# esquematico.net
KiCad netlist of a schematic drawn in EAGLE
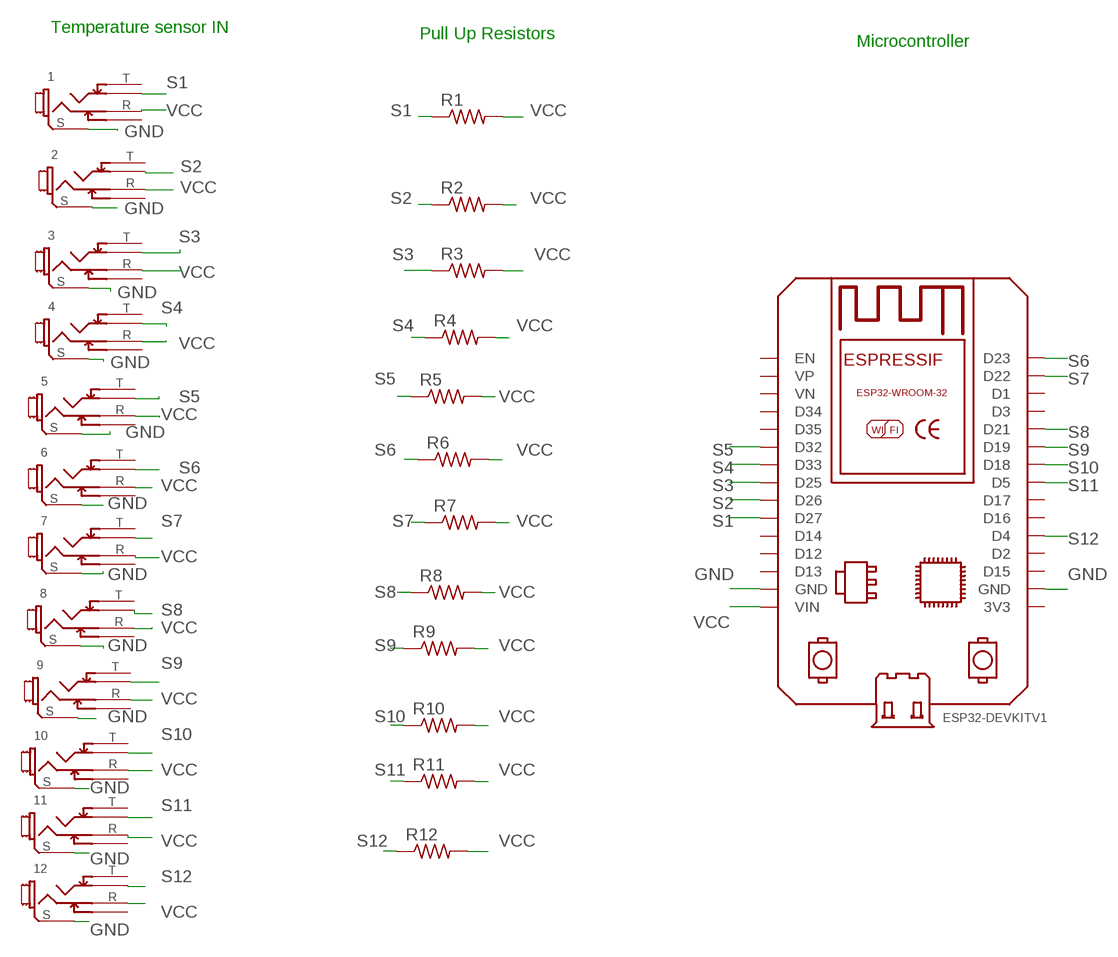
[diagram p0: schematic, sheet 1]

(export (version "E")
  (design (tool "Eeschema 10.0.6"))
  (components
    (comp (ref "1")
      (value "JACK-3.5MM")
      (footprint "eagle-import:JACK-5PINES")
      (libsource (lib "eagle-import") (part "JACK-3.5MM"))
    )
    (comp (ref "2")
      (value "JACK-3.5MM")
      (footprint "eagle-import:JACK-5PINES")
      (libsource (lib "eagle-import") (part "JACK-3.5MM"))
    )
    (comp (ref "3")
      (value "JACK-3.5MM")
      (footprint "eagle-import:JACK-5PINES")
      (libsource (lib "eagle-import") (part "JACK-3.5MM"))
    )
    (comp (ref "4")
      (value "JACK-3.5MM")
      (footprint "eagle-import:JACK-5PINES")
      (libsource (lib "eagle-import") (part "JACK-3.5MM"))
    )
    (comp (ref "5")
      (value "JACK-3.5MM")
      (footprint "eagle-import:JACK-5PINES")
      (libsource (lib "eagle-import") (part "JACK-3.5MM"))
    )
    (comp (ref "6")
      (value "JACK-3.5MM")
      (footprint "eagle-import:JACK-5PINES")
      (libsource (lib "eagle-import") (part "JACK-3.5MM"))
    )
    (comp (ref "7")
      (value "JACK-3.5MM")
      (footprint "eagle-import:JACK-5PINES")
      (libsource (lib "eagle-import") (part "JACK-3.5MM"))
    )
    (comp (ref "8")
      (value "JACK-3.5MM")
      (footprint "eagle-import:JACK-5PINES")
      (libsource (lib "eagle-import") (part "JACK-3.5MM"))
    )
    (comp (ref "9")
      (value "JACK-3.5MM")
      (footprint "eagle-import:JACK-5PINES")
      (libsource (lib "eagle-import") (part "JACK-3.5MM"))
    )
    (comp (ref "10")
      (value "JACK-3.5MM")
      (footprint "eagle-import:JACK-5PINES")
      (libsource (lib "eagle-import") (part "JACK-3.5MM"))
    )
    (comp (ref "11")
      (value "JACK-3.5MM")
      (footprint "eagle-import:JACK-5PINES")
      (libsource (lib "eagle-import") (part "JACK-3.5MM"))
    )
    (comp (ref "12")
      (value "JACK-3.5MM")
      (footprint "eagle-import:JACK-5PINES")
      (libsource (lib "eagle-import") (part "JACK-3.5MM"))
    )
    (comp (ref "BOARD1")
      (value "ESP32DEVKITV1")
      (footprint "eagle-import:ESP32-DEVKITV1")
      (libsource (lib "eagle-import") (part "ESP32DEVKITV1"))
    )
    (comp (ref "R1")
      (value "R-US_M0805")
      (footprint "eagle-import:M0805")
      (libsource (lib "eagle-import") (part "R-US_M0805"))
    )
    (comp (ref "R2")
      (value "R-US_M0805")
      (footprint "eagle-import:M0805")
      (libsource (lib "eagle-import") (part "R-US_M0805"))
    )
    (comp (ref "R3")
      (value "R-US_M0805")
      (footprint "eagle-import:M0805")
      (libsource (lib "eagle-import") (part "R-US_M0805"))
    )
    (comp (ref "R4")
      (value "R-US_M0805")
      (footprint "eagle-import:M0805")
      (libsource (lib "eagle-import") (part "R-US_M0805"))
    )
    (comp (ref "R5")
      (value "R-US_M0805")
      (footprint "eagle-import:M0805")
      (libsource (lib "eagle-import") (part "R-US_M0805"))
    )
    (comp (ref "R6")
      (value "R-US_M0805")
      (footprint "eagle-import:M0805")
      (libsource (lib "eagle-import") (part "R-US_M0805"))
    )
    (comp (ref "R7")
      (value "R-US_M0805")
      (footprint "eagle-import:M0805")
      (libsource (lib "eagle-import") (part "R-US_M0805"))
    )
    (comp (ref "R8")
      (value "R-US_M0805")
      (footprint "eagle-import:M0805")
      (libsource (lib "eagle-import") (part "R-US_M0805"))
    )
    (comp (ref "R9")
      (value "R-US_M0805")
      (footprint "eagle-import:M0805")
      (libsource (lib "eagle-import") (part "R-US_M0805"))
    )
    (comp (ref "R10")
      (value "R-US_M0805")
      (footprint "eagle-import:M0805")
      (libsource (lib "eagle-import") (part "R-US_M0805"))
    )
    (comp (ref "R11")
      (value "R-US_M0805")
      (footprint "eagle-import:M0805")
      (libsource (lib "eagle-import") (part "R-US_M0805"))
    )
    (comp (ref "R12")
      (value "R-US_M0805")
      (footprint "eagle-import:M0805")
      (libsource (lib "eagle-import") (part "R-US_M0805"))
    )
  )
  (nets
    (net (code "1") (name "/GND") (class "Default")
      (node (ref "1") (pin "S") (pinfunction "S_S") (pintype "power_in"))
      (node (ref "10") (pin "S") (pinfunction "S_S") (pintype "power_in"))
      (node (ref "11") (pin "S") (pinfunction "S_S") (pintype "power_in"))
      (node (ref "12") (pin "S") (pinfunction "S_S") (pintype "power_in"))
      (node (ref "2") (pin "S") (pinfunction "S_S") (pintype "power_in"))
      (node (ref "3") (pin "S") (pinfunction "S_S") (pintype "power_in"))
      (node (ref "4") (pin "S") (pinfunction "S_S") (pintype "power_in"))
      (node (ref "5") (pin "S") (pinfunction "S_S") (pintype "power_in"))
      (node (ref "6") (pin "S") (pinfunction "S_S") (pintype "power_in"))
      (node (ref "7") (pin "S") (pinfunction "S_S") (pintype "power_in"))
      (node (ref "8") (pin "S") (pinfunction "S_S") (pintype "power_in"))
      (node (ref "9") (pin "S") (pinfunction "S_S") (pintype "power_in"))
      (node (ref "BOARD1") (pin "GND") (pinfunction "GND_GND") (pintype "bidirectional"))
      (node (ref "BOARD1") (pin "GND@1") (pinfunction "GND_GND@1") (pintype "bidirectional"))
    )
    (net (code "2") (name "/S1") (class "Default")
      (node (ref "1") (pin "T") (pinfunction "T_T") (pintype "bidirectional"))
      (node (ref "BOARD1") (pin "D27") (pinfunction "D27_D27") (pintype "bidirectional"))
      (node (ref "R1") (pin "1") (pinfunction "1_1") (pintype "passive"))
    )
    (net (code "3") (name "/S2") (class "Default")
      (node (ref "2") (pin "T") (pinfunction "T_T") (pintype "bidirectional"))
      (node (ref "BOARD1") (pin "D26") (pinfunction "D26_D26") (pintype "bidirectional"))
      (node (ref "R2") (pin "1") (pinfunction "1_1") (pintype "passive"))
    )
    (net (code "4") (name "/S3") (class "Default")
      (node (ref "3") (pin "T") (pinfunction "T_T") (pintype "bidirectional"))
      (node (ref "BOARD1") (pin "D25") (pinfunction "D25_D25") (pintype "bidirectional"))
      (node (ref "R3") (pin "1") (pinfunction "1_1") (pintype "passive"))
    )
    (net (code "5") (name "/S4") (class "Default")
      (node (ref "4") (pin "T") (pinfunction "T_T") (pintype "bidirectional"))
      (node (ref "BOARD1") (pin "D33") (pinfunction "D33_D33") (pintype "bidirectional"))
      (node (ref "R4") (pin "1") (pinfunction "1_1") (pintype "passive"))
    )
    (net (code "6") (name "/S5") (class "Default")
      (node (ref "5") (pin "T") (pinfunction "T_T") (pintype "bidirectional"))
      (node (ref "BOARD1") (pin "D32") (pinfunction "D32_D32") (pintype "bidirectional"))
      (node (ref "R5") (pin "1") (pinfunction "1_1") (pintype "passive"))
    )
    (net (code "7") (name "/S6") (class "Default")
      (node (ref "6") (pin "T") (pinfunction "T_T") (pintype "bidirectional"))
      (node (ref "BOARD1") (pin "D23") (pinfunction "D23_D23") (pintype "bidirectional"))
      (node (ref "R6") (pin "1") (pinfunction "1_1") (pintype "passive"))
    )
    (net (code "8") (name "/S7") (class "Default")
      (node (ref "7") (pin "T") (pinfunction "T_T") (pintype "bidirectional"))
      (node (ref "BOARD1") (pin "D22") (pinfunction "D22_D22") (pintype "bidirectional"))
      (node (ref "R7") (pin "1") (pinfunction "1_1") (pintype "passive"))
    )
    (net (code "9") (name "/S8") (class "Default")
      (node (ref "8") (pin "T") (pinfunction "T_T") (pintype "bidirectional"))
      (node (ref "BOARD1") (pin "D21") (pinfunction "D21_D21") (pintype "bidirectional"))
      (node (ref "R8") (pin "1") (pinfunction "1_1") (pintype "passive"))
    )
    (net (code "10") (name "/S9") (class "Default")
      (node (ref "9") (pin "T") (pinfunction "T_T") (pintype "bidirectional"))
      (node (ref "BOARD1") (pin "D19") (pinfunction "D19_D19") (pintype "bidirectional"))
      (node (ref "R9") (pin "1") (pinfunction "1_1") (pintype "passive"))
    )
    (net (code "11") (name "/S10") (class "Default")
      (node (ref "10") (pin "T") (pinfunction "T_T") (pintype "bidirectional"))
      (node (ref "BOARD1") (pin "D18") (pinfunction "D18_D18") (pintype "bidirectional"))
      (node (ref "R10") (pin "1") (pinfunction "1_1") (pintype "passive"))
    )
    (net (code "12") (name "/S11") (class "Default")
      (node (ref "11") (pin "T") (pinfunction "T_T") (pintype "bidirectional"))
      (node (ref "BOARD1") (pin "D5") (pinfunction "D5_D5") (pintype "bidirectional"))
      (node (ref "R11") (pin "1") (pinfunction "1_1") (pintype "passive"))
    )
    (net (code "13") (name "/S12") (class "Default")
      (node (ref "12") (pin "T") (pinfunction "T_T") (pintype "bidirectional"))
      (node (ref "BOARD1") (pin "D4") (pinfunction "D4_D4") (pintype "bidirectional"))
      (node (ref "R12") (pin "1") (pinfunction "1_1") (pintype "passive"))
    )
    (net (code "14") (name "/VCC") (class "Default")
      (node (ref "1") (pin "R") (pinfunction "R_R") (pintype "bidirectional"))
      (node (ref "10") (pin "R") (pinfunction "R_R") (pintype "bidirectional"))
      (node (ref "11") (pin "R") (pinfunction "R_R") (pintype "bidirectional"))
      (node (ref "12") (pin "R") (pinfunction "R_R") (pintype "bidirectional"))
      (node (ref "2") (pin "R") (pinfunction "R_R") (pintype "bidirectional"))
      (node (ref "3") (pin "R") (pinfunction "R_R") (pintype "bidirectional"))
      (node (ref "4") (pin "R") (pinfunction "R_R") (pintype "bidirectional"))
      (node (ref "5") (pin "R") (pinfunction "R_R") (pintype "bidirectional"))
      (node (ref "6") (pin "R") (pinfunction "R_R") (pintype "bidirectional"))
      (node (ref "7") (pin "R") (pinfunction "R_R") (pintype "bidirectional"))
      (node (ref "8") (pin "R") (pinfunction "R_R") (pintype "bidirectional"))
      (node (ref "9") (pin "R") (pinfunction "R_R") (pintype "bidirectional"))
      (node (ref "BOARD1") (pin "VIN") (pinfunction "VIN_VIN") (pintype "bidirectional"))
      (node (ref "R1") (pin "2") (pinfunction "2_2") (pintype "passive"))
      (node (ref "R10") (pin "2") (pinfunction "2_2") (pintype "passive"))
      (node (ref "R11") (pin "2") (pinfunction "2_2") (pintype "passive"))
      (node (ref "R12") (pin "2") (pinfunction "2_2") (pintype "passive"))
      (node (ref "R2") (pin "2") (pinfunction "2_2") (pintype "passive"))
      (node (ref "R3") (pin "2") (pinfunction "2_2") (pintype "passive"))
      (node (ref "R4") (pin "2") (pinfunction "2_2") (pintype "passive"))
      (node (ref "R5") (pin "2") (pinfunction "2_2") (pintype "passive"))
      (node (ref "R6") (pin "2") (pinfunction "2_2") (pintype "passive"))
      (node (ref "R7") (pin "2") (pinfunction "2_2") (pintype "passive"))
      (node (ref "R8") (pin "2") (pinfunction "2_2") (pintype "passive"))
      (node (ref "R9") (pin "2") (pinfunction "2_2") (pintype "passive"))
    )
    (net (code "15") (name "unconnected-(1-PadRS)") (class "Default")
      (node (ref "1") (pin "RS") (pinfunction "RS_RS") (pintype "bidirectional"))
    )
    (net (code "16") (name "unconnected-(1-PadTS)") (class "Default")
      (node (ref "1") (pin "TS") (pinfunction "TS_TS") (pintype "bidirectional"))
    )
    (net (code "17") (name "unconnected-(2-PadRS)") (class "Default")
      (node (ref "2") (pin "RS") (pinfunction "RS_RS") (pintype "bidirectional"))
    )
    (net (code "18") (name "unconnected-(2-PadTS)") (class "Default")
      (node (ref "2") (pin "TS") (pinfunction "TS_TS") (pintype "bidirectional"))
    )
    (net (code "19") (name "unconnected-(3-PadRS)") (class "Default")
      (node (ref "3") (pin "RS") (pinfunction "RS_RS") (pintype "bidirectional"))
    )
    (net (code "20") (name "unconnected-(3-PadTS)") (class "Default")
      (node (ref "3") (pin "TS") (pinfunction "TS_TS") (pintype "bidirectional"))
    )
    (net (code "21") (name "unconnected-(4-PadRS)") (class "Default")
      (node (ref "4") (pin "RS") (pinfunction "RS_RS") (pintype "bidirectional"))
    )
    (net (code "22") (name "unconnected-(4-PadTS)") (class "Default")
      (node (ref "4") (pin "TS") (pinfunction "TS_TS") (pintype "bidirectional"))
    )
    (net (code "23") (name "unconnected-(5-PadRS)") (class "Default")
      (node (ref "5") (pin "RS") (pinfunction "RS_RS") (pintype "bidirectional"))
    )
    (net (code "24") (name "unconnected-(5-PadTS)") (class "Default")
      (node (ref "5") (pin "TS") (pinfunction "TS_TS") (pintype "bidirectional"))
    )
    (net (code "25") (name "unconnected-(6-PadRS)") (class "Default")
      (node (ref "6") (pin "RS") (pinfunction "RS_RS") (pintype "bidirectional"))
    )
    (net (code "26") (name "unconnected-(6-PadTS)") (class "Default")
      (node (ref "6") (pin "TS") (pinfunction "TS_TS") (pintype "bidirectional"))
    )
    (net (code "27") (name "unconnected-(7-PadRS)") (class "Default")
      (node (ref "7") (pin "RS") (pinfunction "RS_RS") (pintype "bidirectional"))
    )
    (net (code "28") (name "unconnected-(7-PadTS)") (class "Default")
      (node (ref "7") (pin "TS") (pinfunction "TS_TS") (pintype "bidirectional"))
    )
    (net (code "29") (name "unconnected-(8-PadRS)") (class "Default")
      (node (ref "8") (pin "RS") (pinfunction "RS_RS") (pintype "bidirectional"))
    )
    (net (code "30") (name "unconnected-(8-PadTS)") (class "Default")
      (node (ref "8") (pin "TS") (pinfunction "TS_TS") (pintype "bidirectional"))
    )
    (net (code "31") (name "unconnected-(9-PadRS)") (class "Default")
      (node (ref "9") (pin "RS") (pinfunction "RS_RS") (pintype "bidirectional"))
    )
    (net (code "32") (name "unconnected-(9-PadTS)") (class "Default")
      (node (ref "9") (pin "TS") (pinfunction "TS_TS") (pintype "bidirectional"))
    )
    (net (code "33") (name "unconnected-(10-PadRS)") (class "Default")
      (node (ref "10") (pin "RS") (pinfunction "RS_RS") (pintype "bidirectional"))
    )
    (net (code "34") (name "unconnected-(10-PadTS)") (class "Default")
      (node (ref "10") (pin "TS") (pinfunction "TS_TS") (pintype "bidirectional"))
    )
    (net (code "35") (name "unconnected-(11-PadRS)") (class "Default")
      (node (ref "11") (pin "RS") (pinfunction "RS_RS") (pintype "bidirectional"))
    )
    (net (code "36") (name "unconnected-(11-PadTS)") (class "Default")
      (node (ref "11") (pin "TS") (pinfunction "TS_TS") (pintype "bidirectional"))
    )
    (net (code "37") (name "unconnected-(12-PadRS)") (class "Default")
      (node (ref "12") (pin "RS") (pinfunction "RS_RS") (pintype "bidirectional"))
    )
    (net (code "38") (name "unconnected-(12-PadTS)") (class "Default")
      (node (ref "12") (pin "TS") (pinfunction "TS_TS") (pintype "bidirectional"))
    )
    (net (code "39") (name "unconnected-(BOARD1-Pad3V3)") (class "Default")
      (node (ref "BOARD1") (pin "3V3") (pinfunction "3V3_3V3") (pintype "bidirectional"))
    )
    (net (code "40") (name "unconnected-(BOARD1-PadD1)") (class "Default")
      (node (ref "BOARD1") (pin "D1") (pinfunction "D1_D1") (pintype "bidirectional"))
    )
    (net (code "41") (name "unconnected-(BOARD1-PadD2)") (class "Default")
      (node (ref "BOARD1") (pin "D2") (pinfunction "D2_D2") (pintype "bidirectional"))
    )
    (net (code "42") (name "unconnected-(BOARD1-PadD3)") (class "Default")
      (node (ref "BOARD1") (pin "D3") (pinfunction "D3_D3") (pintype "bidirectional"))
    )
    (net (code "43") (name "unconnected-(BOARD1-PadD12)") (class "Default")
      (node (ref "BOARD1") (pin "D12") (pinfunction "D12_D12") (pintype "bidirectional"))
    )
    (net (code "44") (name "unconnected-(BOARD1-PadD13)") (class "Default")
      (node (ref "BOARD1") (pin "D13") (pinfunction "D13_D13") (pintype "bidirectional"))
    )
    (net (code "45") (name "unconnected-(BOARD1-PadD14)") (class "Default")
      (node (ref "BOARD1") (pin "D14") (pinfunction "D14_D14") (pintype "bidirectional"))
    )
    (net (code "46") (name "unconnected-(BOARD1-PadD15)") (class "Default")
      (node (ref "BOARD1") (pin "D15") (pinfunction "D15_D15") (pintype "bidirectional"))
    )
    (net (code "47") (name "unconnected-(BOARD1-PadD16)") (class "Default")
      (node (ref "BOARD1") (pin "D16") (pinfunction "D16_D16") (pintype "bidirectional"))
    )
    (net (code "48") (name "unconnected-(BOARD1-PadD17)") (class "Default")
      (node (ref "BOARD1") (pin "D17") (pinfunction "D17_D17") (pintype "bidirectional"))
    )
    (net (code "49") (name "unconnected-(BOARD1-PadD34)") (class "Default")
      (node (ref "BOARD1") (pin "D34") (pinfunction "D34_D34") (pintype "bidirectional"))
    )
    (net (code "50") (name "unconnected-(BOARD1-PadD35)") (class "Default")
      (node (ref "BOARD1") (pin "D35") (pinfunction "D35_D35") (pintype "bidirectional"))
    )
    (net (code "51") (name "unconnected-(BOARD1-PadEN)") (class "Default")
      (node (ref "BOARD1") (pin "EN") (pinfunction "EN_EN") (pintype "bidirectional"))
    )
    (net (code "52") (name "unconnected-(BOARD1-PadVN)") (class "Default")
      (node (ref "BOARD1") (pin "VN") (pinfunction "VN_VN") (pintype "bidirectional"))
    )
    (net (code "53") (name "unconnected-(BOARD1-PadVP)") (class "Default")
      (node (ref "BOARD1") (pin "VP") (pinfunction "VP_VP") (pintype "bidirectional"))
    )
  )
)
